# motor_driver.net
KiCad netlist of a schematic drawn in EAGLE
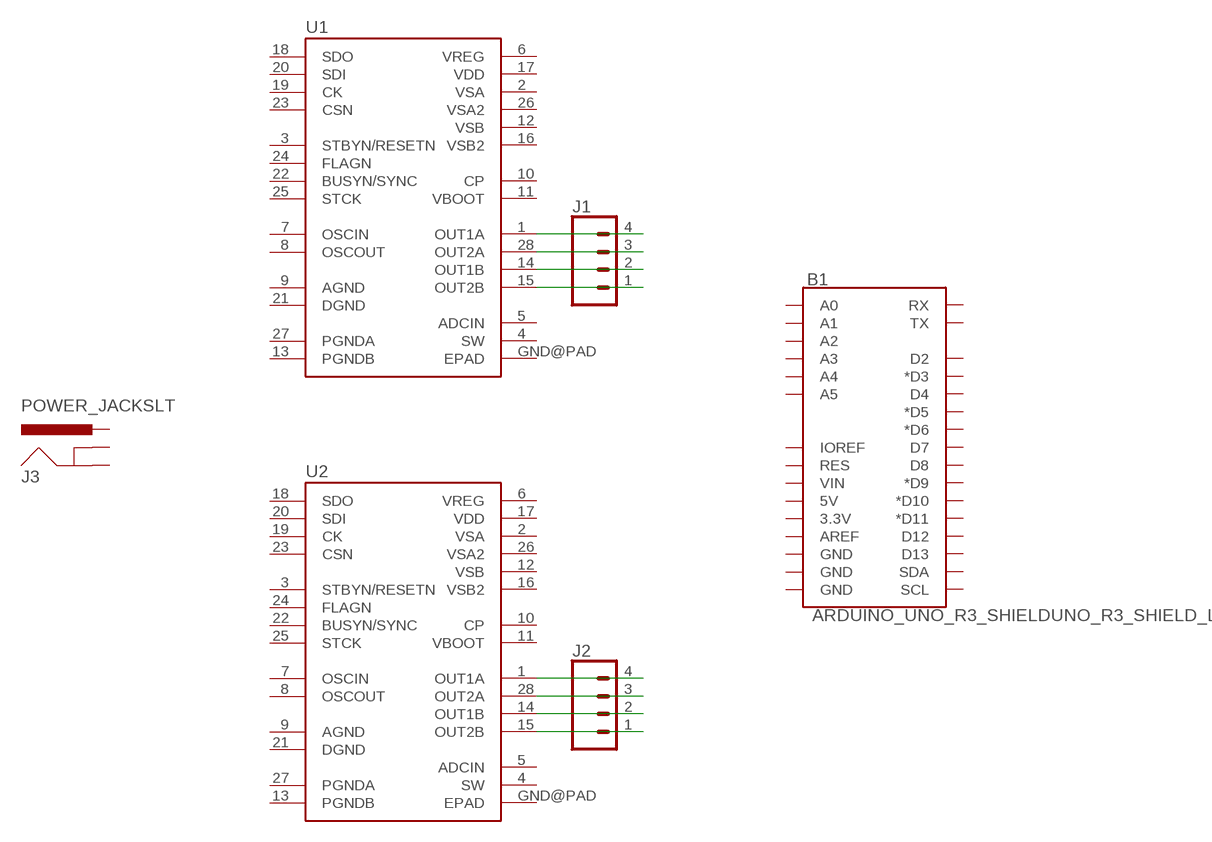
[diagram p0: schematic, sheet 1]

(export (version "E")
  (design (tool "Eeschema 10.0.6"))
  (components
    (comp (ref "B1")
      (value "ARDUINO_UNO_R3_SHIELDUNO_R3_SHIELD_LOCK")
      (footprint "eagle-import:UNO_R3_SHIELD_LOCK")
      (libsource (lib "eagle-import") (part "ARDUINO_UNO_R3_SHIELDUNO_R3_SHIELD_LOCK"))
    )
    (comp (ref "J1")
      (value "CONN_04SCREW")
      (footprint "eagle-import:SCREWTERMINAL-3.5MM-4")
      (libsource (lib "eagle-import") (part "CONN_04SCREW"))
    )
    (comp (ref "J2")
      (value "CONN_04SCREW")
      (footprint "eagle-import:SCREWTERMINAL-3.5MM-4")
      (libsource (lib "eagle-import") (part "CONN_04SCREW"))
    )
    (comp (ref "J3")
      (value "POWER_JACKSLT")
      (footprint "eagle-import:POWER_JACK_SLOT")
      (libsource (lib "eagle-import") (part "POWER_JACKSLT"))
    )
    (comp (ref "U1")
      (value "L6470")
      (footprint "eagle-import:HTSSOP28")
      (libsource (lib "eagle-import") (part "L6470"))
    )
    (comp (ref "U2")
      (value "L6470")
      (footprint "eagle-import:HTSSOP28")
      (libsource (lib "eagle-import") (part "L6470"))
    )
  )
  (nets
    (net (code "1") (name "Net-(U1-OUT1A)") (class "Default")
      (node (ref "J1") (pin "4") (pinfunction "4_4") (pintype "passive"))
      (node (ref "U1") (pin "1") (pinfunction "OUT1A_1") (pintype "bidirectional"))
    )
    (net (code "2") (name "Net-(U1-OUT1B)") (class "Default")
      (node (ref "J1") (pin "2") (pinfunction "2_2") (pintype "passive"))
      (node (ref "U1") (pin "14") (pinfunction "OUT1B_14") (pintype "bidirectional"))
    )
    (net (code "3") (name "Net-(U1-OUT2A)") (class "Default")
      (node (ref "J1") (pin "3") (pinfunction "3_3") (pintype "passive"))
      (node (ref "U1") (pin "28") (pinfunction "OUT2A_28") (pintype "bidirectional"))
    )
    (net (code "4") (name "Net-(U1-OUT2B)") (class "Default")
      (node (ref "J1") (pin "1") (pinfunction "1_1") (pintype "passive"))
      (node (ref "U1") (pin "15") (pinfunction "OUT2B_15") (pintype "bidirectional"))
    )
    (net (code "5") (name "Net-(U2-OUT1A)") (class "Default")
      (node (ref "J2") (pin "4") (pinfunction "4_4") (pintype "passive"))
      (node (ref "U2") (pin "1") (pinfunction "OUT1A_1") (pintype "bidirectional"))
    )
    (net (code "6") (name "Net-(U2-OUT1B)") (class "Default")
      (node (ref "J2") (pin "2") (pinfunction "2_2") (pintype "passive"))
      (node (ref "U2") (pin "14") (pinfunction "OUT1B_14") (pintype "bidirectional"))
    )
    (net (code "7") (name "Net-(U2-OUT2A)") (class "Default")
      (node (ref "J2") (pin "3") (pinfunction "3_3") (pintype "passive"))
      (node (ref "U2") (pin "28") (pinfunction "OUT2A_28") (pintype "bidirectional"))
    )
    (net (code "8") (name "Net-(U2-OUT2B)") (class "Default")
      (node (ref "J2") (pin "1") (pinfunction "1_1") (pintype "passive"))
      (node (ref "U2") (pin "15") (pinfunction "OUT2B_15") (pintype "bidirectional"))
    )
    (net (code "9") (name "unconnected-(B1-*D3-PadD3)") (class "Default")
      (node (ref "B1") (pin "D3") (pinfunction "*D3_D3") (pintype "bidirectional"))
    )
    (net (code "10") (name "unconnected-(B1-*D5-PadD5)") (class "Default")
      (node (ref "B1") (pin "D5") (pinfunction "*D5_D5") (pintype "bidirectional"))
    )
    (net (code "11") (name "unconnected-(B1-*D6-PadD6)") (class "Default")
      (node (ref "B1") (pin "D6") (pinfunction "*D6_D6") (pintype "bidirectional"))
    )
    (net (code "12") (name "unconnected-(B1-*D9-PadD9)") (class "Default")
      (node (ref "B1") (pin "D9") (pinfunction "*D9_D9") (pintype "bidirectional"))
    )
    (net (code "13") (name "unconnected-(B1-*D10-PadD10)") (class "Default")
      (node (ref "B1") (pin "D10") (pinfunction "*D10_D10") (pintype "bidirectional"))
    )
    (net (code "14") (name "unconnected-(B1-*D11-PadD11)") (class "Default")
      (node (ref "B1") (pin "D11") (pinfunction "*D11_D11") (pintype "bidirectional"))
    )
    (net (code "15") (name "unconnected-(B1-GND-PadGND@0)") (class "Default")
      (node (ref "B1") (pin "GND@0") (pinfunction "GND_GND@0") (pintype "bidirectional"))
    )
    (net (code "16") (name "unconnected-(B1-GND-PadGND@1)") (class "Default")
      (node (ref "B1") (pin "GND@1") (pinfunction "GND_GND@1") (pintype "bidirectional"))
    )
    (net (code "17") (name "unconnected-(B1-GND-PadGND@2)") (class "Default")
      (node (ref "B1") (pin "GND@2") (pinfunction "GND_GND@2") (pintype "bidirectional"))
    )
    (net (code "18") (name "unconnected-(B1-Pad3.3V)") (class "Default")
      (node (ref "B1") (pin "3.3V") (pinfunction "3.3V_3.3V") (pintype "bidirectional"))
    )
    (net (code "19") (name "unconnected-(B1-Pad5V)") (class "Default")
      (node (ref "B1") (pin "5V") (pinfunction "5V_5V") (pintype "bidirectional"))
    )
    (net (code "20") (name "unconnected-(B1-PadA0)") (class "Default")
      (node (ref "B1") (pin "A0") (pinfunction "A0_A0") (pintype "bidirectional"))
    )
    (net (code "21") (name "unconnected-(B1-PadA1)") (class "Default")
      (node (ref "B1") (pin "A1") (pinfunction "A1_A1") (pintype "bidirectional"))
    )
    (net (code "22") (name "unconnected-(B1-PadA2)") (class "Default")
      (node (ref "B1") (pin "A2") (pinfunction "A2_A2") (pintype "bidirectional"))
    )
    (net (code "23") (name "unconnected-(B1-PadA3)") (class "Default")
      (node (ref "B1") (pin "A3") (pinfunction "A3_A3") (pintype "bidirectional"))
    )
    (net (code "24") (name "unconnected-(B1-PadA4)") (class "Default")
      (node (ref "B1") (pin "A4") (pinfunction "A4_A4") (pintype "bidirectional"))
    )
    (net (code "25") (name "unconnected-(B1-PadA5)") (class "Default")
      (node (ref "B1") (pin "A5") (pinfunction "A5_A5") (pintype "bidirectional"))
    )
    (net (code "26") (name "unconnected-(B1-PadAREF)") (class "Default")
      (node (ref "B1") (pin "AREF") (pinfunction "AREF_AREF") (pintype "bidirectional"))
    )
    (net (code "27") (name "unconnected-(B1-PadD2)") (class "Default")
      (node (ref "B1") (pin "D2") (pinfunction "D2_D2") (pintype "bidirectional"))
    )
    (net (code "28") (name "unconnected-(B1-PadD4)") (class "Default")
      (node (ref "B1") (pin "D4") (pinfunction "D4_D4") (pintype "bidirectional"))
    )
    (net (code "29") (name "unconnected-(B1-PadD7)") (class "Default")
      (node (ref "B1") (pin "D7") (pinfunction "D7_D7") (pintype "bidirectional"))
    )
    (net (code "30") (name "unconnected-(B1-PadD8)") (class "Default")
      (node (ref "B1") (pin "D8") (pinfunction "D8_D8") (pintype "bidirectional"))
    )
    (net (code "31") (name "unconnected-(B1-PadD12)") (class "Default")
      (node (ref "B1") (pin "D12") (pinfunction "D12_D12") (pintype "bidirectional"))
    )
    (net (code "32") (name "unconnected-(B1-PadD13)") (class "Default")
      (node (ref "B1") (pin "D13") (pinfunction "D13_D13") (pintype "bidirectional"))
    )
    (net (code "33") (name "unconnected-(B1-PadIOREF)") (class "Default")
      (node (ref "B1") (pin "IOREF") (pinfunction "IOREF_IOREF") (pintype "bidirectional"))
    )
    (net (code "34") (name "unconnected-(B1-PadRES)") (class "Default")
      (node (ref "B1") (pin "RES") (pinfunction "RES_RES") (pintype "bidirectional"))
    )
    (net (code "35") (name "unconnected-(B1-PadRX)") (class "Default")
      (node (ref "B1") (pin "RX") (pinfunction "RX_RX") (pintype "bidirectional"))
    )
    (net (code "36") (name "unconnected-(B1-PadSCL)") (class "Default")
      (node (ref "B1") (pin "SCL") (pinfunction "SCL_SCL") (pintype "bidirectional"))
    )
    (net (code "37") (name "unconnected-(B1-PadSDA)") (class "Default")
      (node (ref "B1") (pin "SDA") (pinfunction "SDA_SDA") (pintype "bidirectional"))
    )
    (net (code "38") (name "unconnected-(B1-PadTX)") (class "Default")
      (node (ref "B1") (pin "TX") (pinfunction "TX_TX") (pintype "bidirectional"))
    )
    (net (code "39") (name "unconnected-(B1-PadVIN)") (class "Default")
      (node (ref "B1") (pin "VIN") (pinfunction "VIN_VIN") (pintype "bidirectional"))
    )
    (net (code "40") (name "unconnected-(J3-GND-PadGND@2)") (class "Default")
      (node (ref "J3") (pin "GND@2") (pinfunction "GND_GND@2") (pintype "bidirectional"))
    )
    (net (code "41") (name "unconnected-(J3-GNDBREAK-PadGND@1)") (class "Default")
      (node (ref "J3") (pin "GND@1") (pinfunction "GNDBREAK_GND@1") (pintype "bidirectional"))
    )
    (net (code "42") (name "unconnected-(J3-PadPWR)") (class "Default")
      (node (ref "J3") (pin "PWR") (pinfunction "PWR_PWR") (pintype "bidirectional"))
    )
    (net (code "43") (name "unconnected-(U1-ADCIN-Pad5)") (class "Default")
      (node (ref "U1") (pin "5") (pinfunction "ADCIN_5") (pintype "bidirectional"))
    )
    (net (code "44") (name "unconnected-(U1-AGND-Pad9)") (class "Default")
      (node (ref "U1") (pin "9") (pinfunction "AGND_9") (pintype "bidirectional"))
    )
    (net (code "45") (name "unconnected-(U1-BUSYN{slash}SYNC-Pad22)") (class "Default")
      (node (ref "U1") (pin "22") (pinfunction "BUSYN/SYNC_22") (pintype "bidirectional"))
    )
    (net (code "46") (name "unconnected-(U1-CK-Pad19)") (class "Default")
      (node (ref "U1") (pin "19") (pinfunction "CK_19") (pintype "bidirectional"))
    )
    (net (code "47") (name "unconnected-(U1-CP-Pad10)") (class "Default")
      (node (ref "U1") (pin "10") (pinfunction "CP_10") (pintype "bidirectional"))
    )
    (net (code "48") (name "unconnected-(U1-CSN-Pad23)") (class "Default")
      (node (ref "U1") (pin "23") (pinfunction "CSN_23") (pintype "bidirectional"))
    )
    (net (code "49") (name "unconnected-(U1-DGND-Pad21)") (class "Default")
      (node (ref "U1") (pin "21") (pinfunction "DGND_21") (pintype "bidirectional"))
    )
    (net (code "50") (name "unconnected-(U1-EPAD-PadGND@PAD)") (class "Default")
      (node (ref "U1") (pin "GND@PAD") (pinfunction "EPAD_GND@PAD") (pintype "bidirectional"))
    )
    (net (code "51") (name "unconnected-(U1-FLAGN-Pad24)") (class "Default")
      (node (ref "U1") (pin "24") (pinfunction "FLAGN_24") (pintype "bidirectional"))
    )
    (net (code "52") (name "unconnected-(U1-OSCIN-Pad7)") (class "Default")
      (node (ref "U1") (pin "7") (pinfunction "OSCIN_7") (pintype "bidirectional"))
    )
    (net (code "53") (name "unconnected-(U1-OSCOUT-Pad8)") (class "Default")
      (node (ref "U1") (pin "8") (pinfunction "OSCOUT_8") (pintype "bidirectional"))
    )
    (net (code "54") (name "unconnected-(U1-PGNDA-Pad27)") (class "Default")
      (node (ref "U1") (pin "27") (pinfunction "PGNDA_27") (pintype "bidirectional"))
    )
    (net (code "55") (name "unconnected-(U1-PGNDB-Pad13)") (class "Default")
      (node (ref "U1") (pin "13") (pinfunction "PGNDB_13") (pintype "bidirectional"))
    )
    (net (code "56") (name "unconnected-(U1-SDI-Pad20)") (class "Default")
      (node (ref "U1") (pin "20") (pinfunction "SDI_20") (pintype "bidirectional"))
    )
    (net (code "57") (name "unconnected-(U1-SDO-Pad18)") (class "Default")
      (node (ref "U1") (pin "18") (pinfunction "SDO_18") (pintype "bidirectional"))
    )
    (net (code "58") (name "unconnected-(U1-STBYN{slash}RESETN-Pad3)") (class "Default")
      (node (ref "U1") (pin "3") (pinfunction "STBYN/RESETN_3") (pintype "bidirectional"))
    )
    (net (code "59") (name "unconnected-(U1-STCK-Pad25)") (class "Default")
      (node (ref "U1") (pin "25") (pinfunction "STCK_25") (pintype "bidirectional"))
    )
    (net (code "60") (name "unconnected-(U1-SW-Pad4)") (class "Default")
      (node (ref "U1") (pin "4") (pinfunction "SW_4") (pintype "bidirectional"))
    )
    (net (code "61") (name "unconnected-(U1-VBOOT-Pad11)") (class "Default")
      (node (ref "U1") (pin "11") (pinfunction "VBOOT_11") (pintype "bidirectional"))
    )
    (net (code "62") (name "unconnected-(U1-VDD-Pad17)") (class "Default")
      (node (ref "U1") (pin "17") (pinfunction "VDD_17") (pintype "bidirectional"))
    )
    (net (code "63") (name "unconnected-(U1-VREG-Pad6)") (class "Default")
      (node (ref "U1") (pin "6") (pinfunction "VREG_6") (pintype "bidirectional"))
    )
    (net (code "64") (name "unconnected-(U1-VSA-Pad2)") (class "Default")
      (node (ref "U1") (pin "2") (pinfunction "VSA_2") (pintype "bidirectional"))
    )
    (net (code "65") (name "unconnected-(U1-VSA2-Pad26)") (class "Default")
      (node (ref "U1") (pin "26") (pinfunction "VSA2_26") (pintype "bidirectional"))
    )
    (net (code "66") (name "unconnected-(U1-VSB-Pad12)") (class "Default")
      (node (ref "U1") (pin "12") (pinfunction "VSB_12") (pintype "bidirectional"))
    )
    (net (code "67") (name "unconnected-(U1-VSB2-Pad16)") (class "Default")
      (node (ref "U1") (pin "16") (pinfunction "VSB2_16") (pintype "bidirectional"))
    )
    (net (code "68") (name "unconnected-(U2-ADCIN-Pad5)") (class "Default")
      (node (ref "U2") (pin "5") (pinfunction "ADCIN_5") (pintype "bidirectional"))
    )
    (net (code "69") (name "unconnected-(U2-AGND-Pad9)") (class "Default")
      (node (ref "U2") (pin "9") (pinfunction "AGND_9") (pintype "bidirectional"))
    )
    (net (code "70") (name "unconnected-(U2-BUSYN{slash}SYNC-Pad22)") (class "Default")
      (node (ref "U2") (pin "22") (pinfunction "BUSYN/SYNC_22") (pintype "bidirectional"))
    )
    (net (code "71") (name "unconnected-(U2-CK-Pad19)") (class "Default")
      (node (ref "U2") (pin "19") (pinfunction "CK_19") (pintype "bidirectional"))
    )
    (net (code "72") (name "unconnected-(U2-CP-Pad10)") (class "Default")
      (node (ref "U2") (pin "10") (pinfunction "CP_10") (pintype "bidirectional"))
    )
    (net (code "73") (name "unconnected-(U2-CSN-Pad23)") (class "Default")
      (node (ref "U2") (pin "23") (pinfunction "CSN_23") (pintype "bidirectional"))
    )
    (net (code "74") (name "unconnected-(U2-DGND-Pad21)") (class "Default")
      (node (ref "U2") (pin "21") (pinfunction "DGND_21") (pintype "bidirectional"))
    )
    (net (code "75") (name "unconnected-(U2-EPAD-PadGND@PAD)") (class "Default")
      (node (ref "U2") (pin "GND@PAD") (pinfunction "EPAD_GND@PAD") (pintype "bidirectional"))
    )
    (net (code "76") (name "unconnected-(U2-FLAGN-Pad24)") (class "Default")
      (node (ref "U2") (pin "24") (pinfunction "FLAGN_24") (pintype "bidirectional"))
    )
    (net (code "77") (name "unconnected-(U2-OSCIN-Pad7)") (class "Default")
      (node (ref "U2") (pin "7") (pinfunction "OSCIN_7") (pintype "bidirectional"))
    )
    (net (code "78") (name "unconnected-(U2-OSCOUT-Pad8)") (class "Default")
      (node (ref "U2") (pin "8") (pinfunction "OSCOUT_8") (pintype "bidirectional"))
    )
    (net (code "79") (name "unconnected-(U2-PGNDA-Pad27)") (class "Default")
      (node (ref "U2") (pin "27") (pinfunction "PGNDA_27") (pintype "bidirectional"))
    )
    (net (code "80") (name "unconnected-(U2-PGNDB-Pad13)") (class "Default")
      (node (ref "U2") (pin "13") (pinfunction "PGNDB_13") (pintype "bidirectional"))
    )
    (net (code "81") (name "unconnected-(U2-SDI-Pad20)") (class "Default")
      (node (ref "U2") (pin "20") (pinfunction "SDI_20") (pintype "bidirectional"))
    )
    (net (code "82") (name "unconnected-(U2-SDO-Pad18)") (class "Default")
      (node (ref "U2") (pin "18") (pinfunction "SDO_18") (pintype "bidirectional"))
    )
    (net (code "83") (name "unconnected-(U2-STBYN{slash}RESETN-Pad3)") (class "Default")
      (node (ref "U2") (pin "3") (pinfunction "STBYN/RESETN_3") (pintype "bidirectional"))
    )
    (net (code "84") (name "unconnected-(U2-STCK-Pad25)") (class "Default")
      (node (ref "U2") (pin "25") (pinfunction "STCK_25") (pintype "bidirectional"))
    )
    (net (code "85") (name "unconnected-(U2-SW-Pad4)") (class "Default")
      (node (ref "U2") (pin "4") (pinfunction "SW_4") (pintype "bidirectional"))
    )
    (net (code "86") (name "unconnected-(U2-VBOOT-Pad11)") (class "Default")
      (node (ref "U2") (pin "11") (pinfunction "VBOOT_11") (pintype "bidirectional"))
    )
    (net (code "87") (name "unconnected-(U2-VDD-Pad17)") (class "Default")
      (node (ref "U2") (pin "17") (pinfunction "VDD_17") (pintype "bidirectional"))
    )
    (net (code "88") (name "unconnected-(U2-VREG-Pad6)") (class "Default")
      (node (ref "U2") (pin "6") (pinfunction "VREG_6") (pintype "bidirectional"))
    )
    (net (code "89") (name "unconnected-(U2-VSA-Pad2)") (class "Default")
      (node (ref "U2") (pin "2") (pinfunction "VSA_2") (pintype "bidirectional"))
    )
    (net (code "90") (name "unconnected-(U2-VSA2-Pad26)") (class "Default")
      (node (ref "U2") (pin "26") (pinfunction "VSA2_26") (pintype "bidirectional"))
    )
    (net (code "91") (name "unconnected-(U2-VSB-Pad12)") (class "Default")
      (node (ref "U2") (pin "12") (pinfunction "VSB_12") (pintype "bidirectional"))
    )
    (net (code "92") (name "unconnected-(U2-VSB2-Pad16)") (class "Default")
      (node (ref "U2") (pin "16") (pinfunction "VSB2_16") (pintype "bidirectional"))
    )
  )
)
